# cyclops_r2b.net
KiCad netlist of a schematic drawn in EAGLE
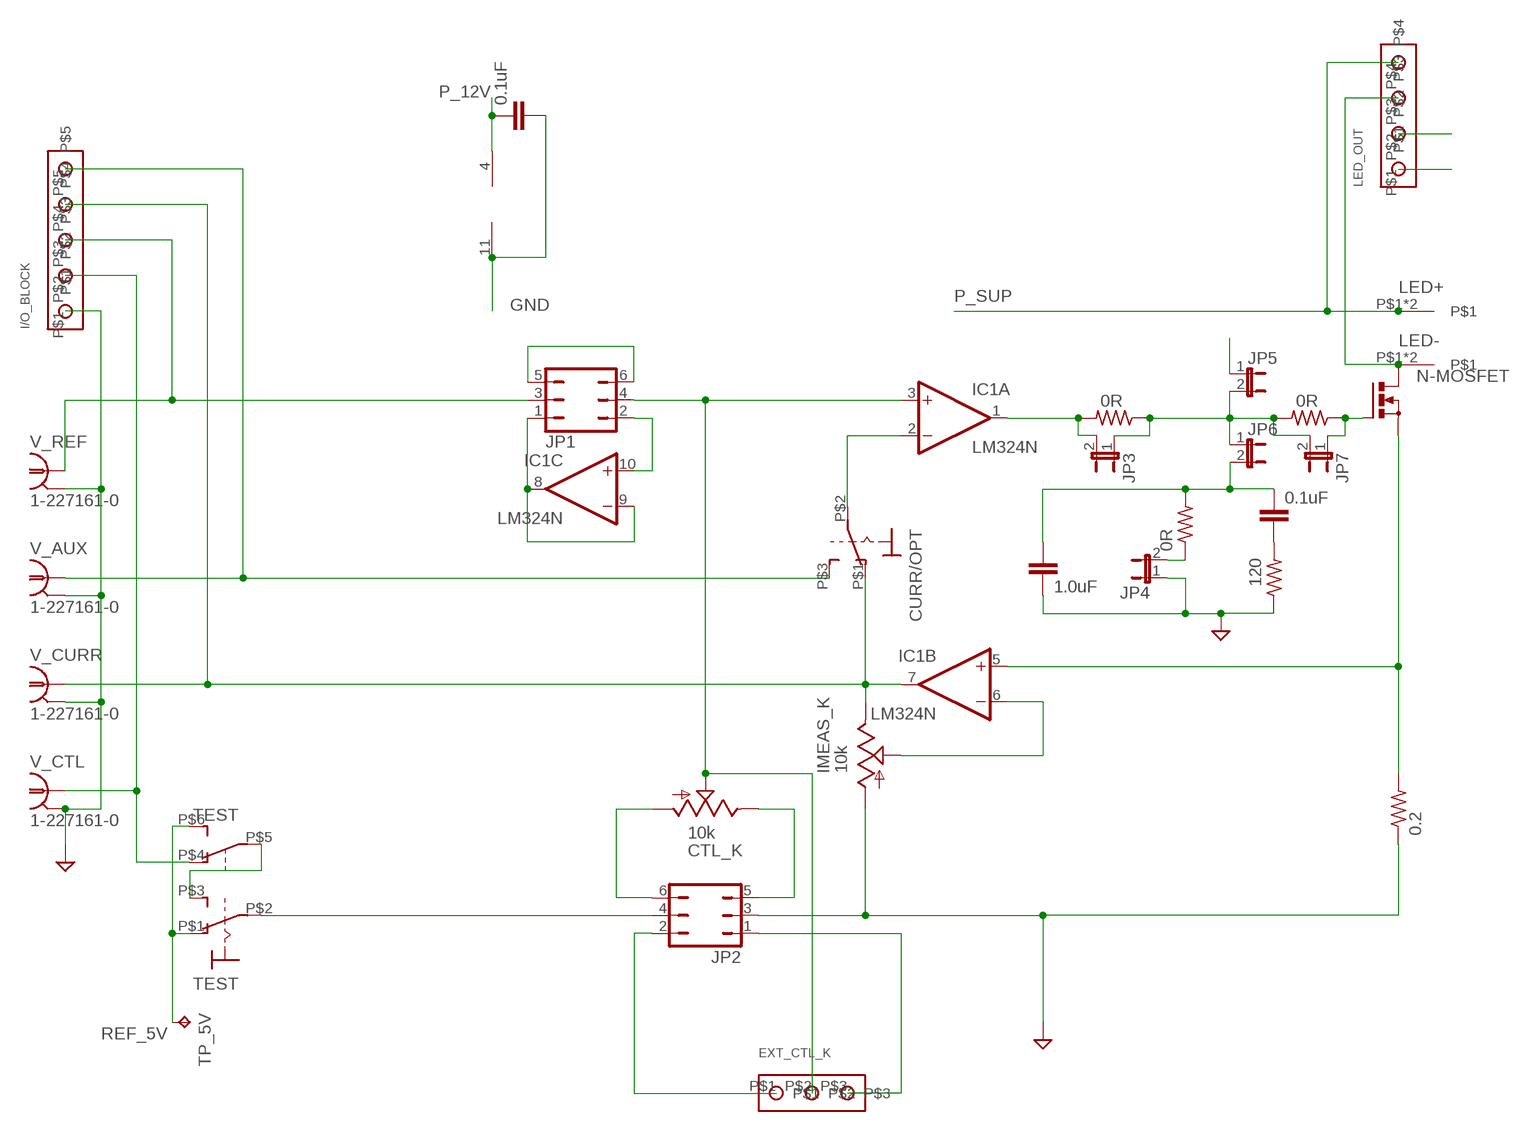
[diagram p0: schematic, sheet 1]
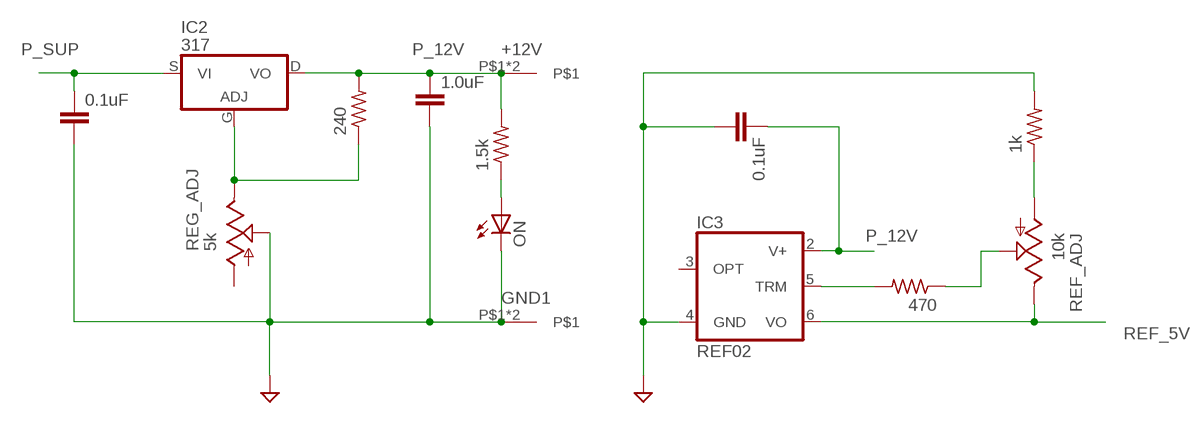
[diagram p1: schematic, sheet 2]
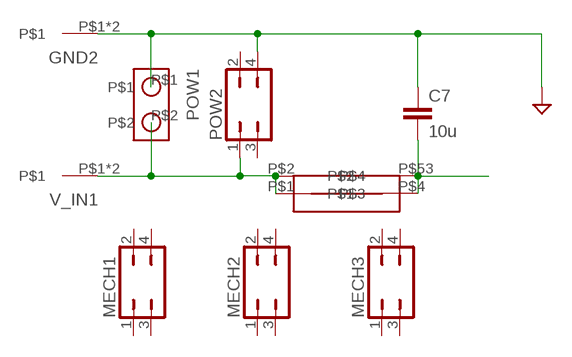
[diagram p2: schematic, sheet 3]

(export (version "E")
  (design (tool "Eeschema 10.0.6"))
  (components
    (comp (ref "+12V")
      (value "BANANA_TO_BOARD")
      (footprint "eagle-import:BANANA_TO_BOARD")
      (libsource (lib "eagle-import") (part "BANANA_TO_BOARD"))
    )
    (comp (ref "C4")
      (value "0.1uF")
      (footprint "eagle-import:C050-024X044")
      (libsource (lib "eagle-import") (part "C-EU050-024X044"))
    )
    (comp (ref "C5")
      (value "1.0uF")
      (footprint "eagle-import:C025-024X044")
      (libsource (lib "eagle-import") (part "C-EU025-024X044"))
    )
    (comp (ref "C6")
      (value "0.1uF")
      (footprint "eagle-import:C050-024X044")
      (libsource (lib "eagle-import") (part "C-EU050-024X044"))
    )
    (comp (ref "GND1")
      (value "BANANA_TO_BOARD")
      (footprint "eagle-import:BANANA_TO_BOARD")
      (libsource (lib "eagle-import") (part "BANANA_TO_BOARD"))
    )
    (comp (ref "IC2")
      (value "317")
      (footprint "eagle-import:TO220BH")
      (libsource (lib "eagle-import") (part "317"))
    )
    (comp (ref "IC3")
      (value "REF02")
      (footprint "eagle-import:DIL08-OVAL")
      (libsource (lib "eagle-import") (part "REF02DIL08-LONG"))
    )
    (comp (ref "ON")
      (value "LED3MM")
      (footprint "eagle-import:LED3MM")
      (libsource (lib "eagle-import") (part "LED3MM"))
    )
    (comp (ref "R5")
      (value "240")
      (footprint "eagle-import:0207_7")
      (libsource (lib "eagle-import") (part "R-US_0207/7"))
    )
    (comp (ref "R6")
      (value "1.5k")
      (footprint "eagle-import:0207_7")
      (libsource (lib "eagle-import") (part "R-US_0207/7"))
    )
    (comp (ref "R7")
      (value "470")
      (footprint "eagle-import:0207_7")
      (libsource (lib "eagle-import") (part "R-US_0207/7"))
    )
    (comp (ref "R8")
      (value "1k")
      (footprint "eagle-import:0207_7")
      (libsource (lib "eagle-import") (part "R-US_0207/7"))
    )
    (comp (ref "REF_ADJ")
      (value "10k")
      (footprint "eagle-import:RJ6S")
      (libsource (lib "eagle-import") (part "TRIM_US-RJ6S"))
    )
    (comp (ref "REG_ADJ")
      (value "5k")
      (footprint "eagle-import:RJ6S")
      (libsource (lib "eagle-import") (part "TRIM_US-RJ6S"))
    )
    (comp (ref "C7")
      (value "10u")
      (footprint "eagle-import:C025-024X044")
      (libsource (lib "eagle-import") (part "C-EU025-024X044"))
    )
    (comp (ref "GND2")
      (value "BANANA_TO_BOARD")
      (footprint "eagle-import:BANANA_TO_BOARD")
      (libsource (lib "eagle-import") (part "BANANA_TO_BOARD"))
    )
    (comp (ref "MECH1")
      (value "JP2Q")
      (footprint "eagle-import:JP2Q")
      (libsource (lib "eagle-import") (part "JP2Q"))
    )
    (comp (ref "MECH2")
      (value "JP2Q")
      (footprint "eagle-import:JP2Q")
      (libsource (lib "eagle-import") (part "JP2Q"))
    )
    (comp (ref "MECH3")
      (value "JP2Q")
      (footprint "eagle-import:JP2Q")
      (libsource (lib "eagle-import") (part "JP2Q"))
    )
    (comp (ref "POW1")
      (value "SCREW2")
      (footprint "eagle-import:SCREW2")
      (libsource (lib "eagle-import") (part "SCREW2"))
    )
    (comp (ref "POW2")
      (value "JP2Q")
      (footprint "eagle-import:JP2Q")
      (libsource (lib "eagle-import") (part "JP2Q"))
    )
    (comp (ref "U$1")
      (value "FUSE >2A")
      (footprint "eagle-import:NXT-FUSE")
      (libsource (lib "eagle-import") (part "NXT-FUSE"))
    )
    (comp (ref "V_IN1")
      (value "BANANA_TO_BOARD")
      (footprint "eagle-import:BANANA_TO_BOARD")
      (libsource (lib "eagle-import") (part "BANANA_TO_BOARD"))
    )
    (comp (ref "C1")
      (value "0.1uF")
      (footprint "eagle-import:C050-024X044")
      (libsource (lib "eagle-import") (part "C-EU050-024X044"))
    )
    (comp (ref "C2")
      (value "1.0uF")
      (footprint "eagle-import:C025-024X044")
      (libsource (lib "eagle-import") (part "C-EU025-024X044"))
    )
    (comp (ref "C3")
      (value "0.1uF")
      (footprint "eagle-import:C050-024X044")
      (libsource (lib "eagle-import") (part "C-EU050-024X044"))
    )
    (comp (ref "CTL_K")
      (value "10k")
      (footprint "eagle-import:RJ6S")
      (libsource (lib "eagle-import") (part "TRIM_US-RJ6S"))
    )
    (comp (ref "CURR/OPT")
      (value "SPST_SWITCH")
      (footprint "eagle-import:A_TOGGLE_SPST")
      (libsource (lib "eagle-import") (part "SPST_SWITCH"))
    )
    (comp (ref "EXT_CTL_K")
      (value "SCREW3")
      (footprint "eagle-import:SCREW3")
      (libsource (lib "eagle-import") (part "SCREW3"))
    )
    (comp (ref "I/O_BLOCK")
      (value "SCREW5")
      (footprint "eagle-import:SCREW5")
      (libsource (lib "eagle-import") (part "SCREW5"))
    )
    (comp (ref "IC1")
      (value "LM324N")
      (footprint "eagle-import:DIL14")
      (libsource (lib "eagle-import") (part "LM324N"))
    )
    (comp (ref "IMEAS_K")
      (value "10k")
      (footprint "eagle-import:RJ6S")
      (libsource (lib "eagle-import") (part "TRIM_US-RJ6S"))
    )
    (comp (ref "JP1")
      (value "JP3Q")
      (footprint "eagle-import:JP3Q")
      (libsource (lib "eagle-import") (part "JP3Q"))
    )
    (comp (ref "JP2")
      (value "JP3Q")
      (footprint "eagle-import:JP3Q")
      (libsource (lib "eagle-import") (part "JP3Q"))
    )
    (comp (ref "JP3")
      (value "JP1E")
      (footprint "eagle-import:JP1")
      (libsource (lib "eagle-import") (part "JP1E"))
    )
    (comp (ref "JP4")
      (value "JP1E")
      (footprint "eagle-import:JP1")
      (libsource (lib "eagle-import") (part "JP1E"))
    )
    (comp (ref "JP5")
      (value "JP1E")
      (footprint "eagle-import:JP1")
      (libsource (lib "eagle-import") (part "JP1E"))
    )
    (comp (ref "JP6")
      (value "JP1E")
      (footprint "eagle-import:JP1")
      (libsource (lib "eagle-import") (part "JP1E"))
    )
    (comp (ref "JP7")
      (value "JP1E")
      (footprint "eagle-import:JP1")
      (libsource (lib "eagle-import") (part "JP1E"))
    )
    (comp (ref "LED+")
      (value "BANANA_TO_BOARD")
      (footprint "eagle-import:BANANA_TO_BOARD")
      (libsource (lib "eagle-import") (part "BANANA_TO_BOARD"))
    )
    (comp (ref "LED-")
      (value "BANANA_TO_BOARD")
      (footprint "eagle-import:BANANA_TO_BOARD")
      (libsource (lib "eagle-import") (part "BANANA_TO_BOARD"))
    )
    (comp (ref "LED_OUT")
      (value "SCREW4")
      (footprint "eagle-import:SCREW4")
      (libsource (lib "eagle-import") (part "SCREW4"))
    )
    (comp (ref "N-MOSFET")
      (value "PMOSFET_NTO220BH")
      (footprint "eagle-import:TO220BH")
      (libsource (lib "eagle-import") (part "PMOSFET_NTO220BH"))
    )
    (comp (ref "R1")
      (value "0R")
      (footprint "eagle-import:0207_7")
      (libsource (lib "eagle-import") (part "R-US_0207/7"))
    )
    (comp (ref "R2")
      (value "0R")
      (footprint "eagle-import:0207_7")
      (libsource (lib "eagle-import") (part "R-US_0207/7"))
    )
    (comp (ref "R3")
      (value "120")
      (footprint "eagle-import:0207_7")
      (libsource (lib "eagle-import") (part "R-US_0207/7"))
    )
    (comp (ref "R4")
      (value "0R")
      (footprint "eagle-import:0207_7")
      (libsource (lib "eagle-import") (part "R-US_0207/7"))
    )
    (comp (ref "R_CURR")
      (value "0.2")
      (footprint "eagle-import:IMEAS_R")
      (libsource (lib "eagle-import") (part "R-US_"))
    )
    (comp (ref "TEST")
      (value "SP3T_SWITCH")
      (footprint "eagle-import:320-938")
      (libsource (lib "eagle-import") (part "SP3T_SWITCH"))
    )
    (comp (ref "TP_5V")
      (value "TPPAD1-13")
      (footprint "eagle-import:P1-13")
      (libsource (lib "eagle-import") (part "TPPAD1-13"))
    )
    (comp (ref "V_AUX")
      (value "1-227161-0")
      (footprint "eagle-import:AMP_227161")
      (libsource (lib "eagle-import") (part "?2271611--0"))
    )
    (comp (ref "V_CTL")
      (value "1-227161-0")
      (footprint "eagle-import:AMP_227161")
      (libsource (lib "eagle-import") (part "?2271611--0"))
    )
    (comp (ref "V_CURR")
      (value "1-227161-0")
      (footprint "eagle-import:AMP_227161")
      (libsource (lib "eagle-import") (part "?2271611--0"))
    )
    (comp (ref "V_REF")
      (value "1-227161-0")
      (footprint "eagle-import:AMP_227161")
      (libsource (lib "eagle-import") (part "?2271611--0"))
    )
  )
  (nets
    (net (code "1") (name "GND") (class "Default")
      (node (ref "C1") (pin "2") (pinfunction "2_2") (pintype "passive"))
      (node (ref "C2") (pin "2") (pinfunction "2_2") (pintype "passive"))
      (node (ref "C4") (pin "2") (pinfunction "2_2") (pintype "passive"))
      (node (ref "C5") (pin "2") (pinfunction "2_2") (pintype "passive"))
      (node (ref "C6") (pin "2") (pinfunction "2_2") (pintype "passive"))
      (node (ref "C7") (pin "1") (pinfunction "1_1") (pintype "passive"))
      (node (ref "GND1") (pin "P$1") (pinfunction "P$1_P$1") (pintype "bidirectional"))
      (node (ref "GND1") (pin "P$2") (pinfunction "P$1_P$2") (pintype "bidirectional"))
      (node (ref "GND2") (pin "P$1") (pinfunction "P$1_P$1") (pintype "bidirectional"))
      (node (ref "GND2") (pin "P$2") (pinfunction "P$1_P$2") (pintype "bidirectional"))
      (node (ref "I/O_BLOCK") (pin "P$1") (pinfunction "P$1_P$1") (pintype "bidirectional"))
      (node (ref "IC1") (pin "11") (pinfunction "V-_11") (pintype "power_in"))
      (node (ref "IC3") (pin "4") (pinfunction "GND_4") (pintype "power_in"))
      (node (ref "IMEAS_K") (pin "A") (pinfunction "A_A") (pintype "passive"))
      (node (ref "JP2") (pin "3") (pinfunction "3_3") (pintype "passive"))
      (node (ref "JP4") (pin "1") (pinfunction "1_1") (pintype "passive"))
      (node (ref "LED_OUT") (pin "P$1") (pinfunction "P$1_P$1") (pintype "bidirectional"))
      (node (ref "ON") (pin "K") (pinfunction "C_K") (pintype "passive"))
      (node (ref "POW1") (pin "P$1") (pinfunction "P$1_P$1") (pintype "bidirectional"))
      (node (ref "POW2") (pin "4") (pinfunction "4_4") (pintype "passive"))
      (node (ref "R3") (pin "1") (pinfunction "1_1") (pintype "passive"))
      (node (ref "R8") (pin "2") (pinfunction "2_2") (pintype "passive"))
      (node (ref "REG_ADJ") (pin "S") (pinfunction "S_S") (pintype "passive"))
      (node (ref "R_CURR") (pin "1") (pinfunction "1_1") (pintype "passive"))
      (node (ref "V_AUX") (pin "2") (pinfunction "GND_2") (pintype "power_in"))
      (node (ref "V_CTL") (pin "2") (pinfunction "GND_2") (pintype "power_in"))
      (node (ref "V_CURR") (pin "2") (pinfunction "GND_2") (pintype "power_in"))
      (node (ref "V_REF") (pin "2") (pinfunction "GND_2") (pintype "power_in"))
    )
    (net (code "2") (name "Net-(C2-Pad1)") (class "Default")
      (node (ref "C2") (pin "1") (pinfunction "1_1") (pintype "passive"))
      (node (ref "C3") (pin "1") (pinfunction "1_1") (pintype "passive"))
      (node (ref "JP6") (pin "2") (pinfunction "2_2") (pintype "passive"))
      (node (ref "R2") (pin "2") (pinfunction "2_2") (pintype "passive"))
    )
    (net (code "3") (name "Net-(C3-Pad2)") (class "Default")
      (node (ref "C3") (pin "2") (pinfunction "2_2") (pintype "passive"))
      (node (ref "R3") (pin "2") (pinfunction "2_2") (pintype "passive"))
    )
    (net (code "4") (name "Net-(CTL_K-PadA)") (class "Default")
      (node (ref "CTL_K") (pin "A") (pinfunction "A_A") (pintype "passive"))
      (node (ref "JP2") (pin "6") (pinfunction "6_6") (pintype "passive"))
    )
    (net (code "5") (name "Net-(CTL_K-PadE)") (class "Default")
      (node (ref "CTL_K") (pin "E") (pinfunction "E_E") (pintype "passive"))
      (node (ref "JP2") (pin "5") (pinfunction "5_5") (pintype "passive"))
    )
    (net (code "6") (name "Net-(CURR/OPT-O)") (class "Default")
      (node (ref "CURR/OPT") (pin "P$1") (pinfunction "O_P$1") (pintype "passive"))
      (node (ref "I/O_BLOCK") (pin "P$4") (pinfunction "P$4_P$4") (pintype "bidirectional"))
      (node (ref "IC1") (pin "7") (pinfunction "OUT_7") (pintype "output"))
      (node (ref "IMEAS_K") (pin "E") (pinfunction "E_E") (pintype "passive"))
      (node (ref "V_CURR") (pin "1") (pinfunction "1_1") (pintype "passive"))
    )
    (net (code "7") (name "Net-(CURR/OPT-P)") (class "Default")
      (node (ref "CURR/OPT") (pin "P$2") (pinfunction "P_P$2") (pintype "passive"))
      (node (ref "IC1") (pin "2") (pinfunction "-IN_2") (pintype "input"))
    )
    (net (code "8") (name "Net-(CURR/OPT-S)") (class "Default")
      (node (ref "CURR/OPT") (pin "P$3") (pinfunction "S_P$3") (pintype "passive"))
      (node (ref "I/O_BLOCK") (pin "P$5") (pinfunction "P$5_P$5") (pintype "bidirectional"))
      (node (ref "V_AUX") (pin "1") (pinfunction "1_1") (pintype "passive"))
    )
    (net (code "9") (name "Net-(EXT_CTL_K-PadP$1)") (class "Default")
      (node (ref "EXT_CTL_K") (pin "P$1") (pinfunction "P$1_P$1") (pintype "bidirectional"))
      (node (ref "JP2") (pin "2") (pinfunction "2_2") (pintype "passive"))
    )
    (net (code "10") (name "Net-(EXT_CTL_K-PadP$3)") (class "Default")
      (node (ref "EXT_CTL_K") (pin "P$3") (pinfunction "P$3_P$3") (pintype "bidirectional"))
      (node (ref "JP2") (pin "1") (pinfunction "1_1") (pintype "passive"))
    )
    (net (code "11") (name "Net-(I/O_BLOCK-PadP$3)") (class "Default")
      (node (ref "I/O_BLOCK") (pin "P$3") (pinfunction "P$3_P$3") (pintype "bidirectional"))
      (node (ref "JP1") (pin "3") (pinfunction "3_3") (pintype "passive"))
      (node (ref "V_REF") (pin "1") (pinfunction "1_1") (pintype "passive"))
    )
    (net (code "12") (name "Net-(IC1A-+IN)") (class "Default")
      (node (ref "CTL_K") (pin "S") (pinfunction "S_S") (pintype "passive"))
      (node (ref "EXT_CTL_K") (pin "P$2") (pinfunction "P$2_P$2") (pintype "bidirectional"))
      (node (ref "IC1") (pin "3") (pinfunction "+IN_3") (pintype "input"))
      (node (ref "JP1") (pin "4") (pinfunction "4_4") (pintype "passive"))
    )
    (net (code "13") (name "Net-(IC1A-OUT)") (class "Default")
      (node (ref "IC1") (pin "1") (pinfunction "OUT_1") (pintype "output"))
      (node (ref "JP3") (pin "2") (pinfunction "2_2") (pintype "passive"))
      (node (ref "R1") (pin "2") (pinfunction "2_2") (pintype "passive"))
    )
    (net (code "14") (name "Net-(IC1B-+IN)") (class "Default")
      (node (ref "IC1") (pin "5") (pinfunction "+IN_5") (pintype "input"))
      (node (ref "N-MOSFET") (pin "S") (pinfunction "S_S") (pintype "passive"))
      (node (ref "R_CURR") (pin "2") (pinfunction "2_2") (pintype "passive"))
    )
    (net (code "15") (name "Net-(IC1B--IN)") (class "Default")
      (node (ref "IC1") (pin "6") (pinfunction "-IN_6") (pintype "input"))
      (node (ref "IMEAS_K") (pin "S") (pinfunction "S_S") (pintype "passive"))
    )
    (net (code "16") (name "Net-(IC1C-+IN)") (class "Default")
      (node (ref "IC1") (pin "10") (pinfunction "+IN_10") (pintype "input"))
      (node (ref "JP1") (pin "2") (pinfunction "2_2") (pintype "passive"))
    )
    (net (code "17") (name "Net-(IC1C--IN)") (class "Default")
      (node (ref "IC1") (pin "8") (pinfunction "OUT_8") (pintype "output"))
      (node (ref "IC1") (pin "9") (pinfunction "-IN_9") (pintype "input"))
      (node (ref "JP1") (pin "1") (pinfunction "1_1") (pintype "passive"))
    )
    (net (code "18") (name "Net-(IC2-ADJ)") (class "Default")
      (node (ref "IC2") (pin "G") (pinfunction "ADJ_G") (pintype "input"))
      (node (ref "R5") (pin "1") (pinfunction "1_1") (pintype "passive"))
      (node (ref "REG_ADJ") (pin "E") (pinfunction "E_E") (pintype "passive"))
    )
    (net (code "19") (name "Net-(IC3-TRM)") (class "Default")
      (node (ref "IC3") (pin "5") (pinfunction "TRM_5") (pintype "input"))
      (node (ref "R7") (pin "2") (pinfunction "2_2") (pintype "passive"))
    )
    (net (code "20") (name "Net-(JP1-Pad5)") (class "Default")
      (node (ref "JP1") (pin "5") (pinfunction "5_5") (pintype "passive"))
      (node (ref "JP1") (pin "6") (pinfunction "6_6") (pintype "passive"))
    )
    (net (code "21") (name "Net-(JP3-Pad1)") (class "Default")
      (node (ref "JP3") (pin "1") (pinfunction "1_1") (pintype "passive"))
      (node (ref "JP5") (pin "2") (pinfunction "2_2") (pintype "passive"))
      (node (ref "JP6") (pin "1") (pinfunction "1_1") (pintype "passive"))
      (node (ref "JP7") (pin "2") (pinfunction "2_2") (pintype "passive"))
      (node (ref "R1") (pin "1") (pinfunction "1_1") (pintype "passive"))
      (node (ref "R4") (pin "2") (pinfunction "2_2") (pintype "passive"))
    )
    (net (code "22") (name "Net-(JP4-Pad2)") (class "Default")
      (node (ref "JP4") (pin "2") (pinfunction "2_2") (pintype "passive"))
      (node (ref "R2") (pin "1") (pinfunction "1_1") (pintype "passive"))
    )
    (net (code "23") (name "Net-(JP7-Pad1)") (class "Default")
      (node (ref "JP7") (pin "1") (pinfunction "1_1") (pintype "passive"))
      (node (ref "N-MOSFET") (pin "G") (pinfunction "G_G") (pintype "passive"))
      (node (ref "R4") (pin "1") (pinfunction "1_1") (pintype "passive"))
    )
    (net (code "24") (name "Net-(LED--P$1-PadP$2)") (class "Default")
      (node (ref "LED-") (pin "P$1") (pinfunction "P$1_P$1") (pintype "bidirectional"))
      (node (ref "LED-") (pin "P$2") (pinfunction "P$1_P$2") (pintype "bidirectional"))
      (node (ref "LED_OUT") (pin "P$3") (pinfunction "P$3_P$3") (pintype "bidirectional"))
      (node (ref "N-MOSFET") (pin "D") (pinfunction "D_D") (pintype "passive"))
    )
    (net (code "25") (name "Net-(ON-PadA)") (class "Default")
      (node (ref "ON") (pin "A") (pinfunction "A_A") (pintype "passive"))
      (node (ref "R6") (pin "1") (pinfunction "1_1") (pintype "passive"))
    )
    (net (code "26") (name "Net-(POW1-PadP$2)") (class "Default")
      (node (ref "POW1") (pin "P$2") (pinfunction "P$2_P$2") (pintype "bidirectional"))
      (node (ref "POW2") (pin "1") (pinfunction "1_1") (pintype "passive"))
      (node (ref "U$1") (pin "P$1") (pinfunction "P$1_P$1") (pintype "bidirectional"))
      (node (ref "U$1") (pin "P$2") (pinfunction "P$2_P$2") (pintype "bidirectional"))
      (node (ref "V_IN1") (pin "P$1") (pinfunction "P$1_P$1") (pintype "bidirectional"))
      (node (ref "V_IN1") (pin "P$2") (pinfunction "P$1_P$2") (pintype "bidirectional"))
    )
    (net (code "27") (name "Net-(R7-Pad1)") (class "Default")
      (node (ref "R7") (pin "1") (pinfunction "1_1") (pintype "passive"))
      (node (ref "REF_ADJ") (pin "S") (pinfunction "S_S") (pintype "passive"))
    )
    (net (code "28") (name "Net-(R8-Pad1)") (class "Default")
      (node (ref "R8") (pin "1") (pinfunction "1_1") (pintype "passive"))
      (node (ref "REF_ADJ") (pin "A") (pinfunction "A_A") (pintype "passive"))
    )
    (net (code "29") (name "Net-(TESTA-P)") (class "Default")
      (node (ref "JP2") (pin "4") (pinfunction "4_4") (pintype "passive"))
      (node (ref "TEST") (pin "P$2") (pinfunction "P_P$2") (pintype "passive"))
    )
    (net (code "30") (name "Net-(TESTA-S)") (class "Default")
      (node (ref "TEST") (pin "P$3") (pinfunction "S_P$3") (pintype "passive"))
      (node (ref "TEST") (pin "P$5") (pinfunction "P_P$5") (pintype "passive"))
    )
    (net (code "31") (name "Net-(TESTB-O)") (class "Default")
      (node (ref "I/O_BLOCK") (pin "P$2") (pinfunction "P$2_P$2") (pintype "bidirectional"))
      (node (ref "TEST") (pin "P$4") (pinfunction "O_P$4") (pintype "passive"))
      (node (ref "V_CTL") (pin "1") (pinfunction "1_1") (pintype "passive"))
    )
    (net (code "32") (name "P_12V") (class "Default")
      (node (ref "+12V") (pin "P$1") (pinfunction "P$1_P$1") (pintype "bidirectional"))
      (node (ref "+12V") (pin "P$2") (pinfunction "P$1_P$2") (pintype "bidirectional"))
      (node (ref "C1") (pin "1") (pinfunction "1_1") (pintype "passive"))
      (node (ref "C5") (pin "1") (pinfunction "1_1") (pintype "passive"))
      (node (ref "C6") (pin "1") (pinfunction "1_1") (pintype "passive"))
      (node (ref "IC1") (pin "4") (pinfunction "V+_4") (pintype "power_in"))
      (node (ref "IC2") (pin "D") (pinfunction "VO_D") (pintype "passive"))
      (node (ref "IC3") (pin "2") (pinfunction "V+_2") (pintype "power_in"))
      (node (ref "LED_OUT") (pin "P$2") (pinfunction "P$2_P$2") (pintype "bidirectional"))
      (node (ref "R5") (pin "2") (pinfunction "2_2") (pintype "passive"))
      (node (ref "R6") (pin "2") (pinfunction "2_2") (pintype "passive"))
    )
    (net (code "33") (name "P_SUP") (class "Default")
      (node (ref "C4") (pin "1") (pinfunction "1_1") (pintype "passive"))
      (node (ref "C7") (pin "2") (pinfunction "2_2") (pintype "passive"))
      (node (ref "IC2") (pin "S") (pinfunction "VI_S") (pintype "input"))
      (node (ref "LED+") (pin "P$1") (pinfunction "P$1_P$1") (pintype "bidirectional"))
      (node (ref "LED+") (pin "P$2") (pinfunction "P$1_P$2") (pintype "bidirectional"))
      (node (ref "LED_OUT") (pin "P$4") (pinfunction "P$4_P$4") (pintype "bidirectional"))
      (node (ref "U$1") (pin "P$4") (pinfunction "P$3_P$4") (pintype "bidirectional"))
      (node (ref "U$1") (pin "P$53") (pinfunction "P$4_P$53") (pintype "bidirectional"))
    )
    (net (code "34") (name "REF_5V") (class "Default")
      (node (ref "IC3") (pin "6") (pinfunction "VO_6") (pintype "output"))
      (node (ref "REF_ADJ") (pin "E") (pinfunction "E_E") (pintype "passive"))
      (node (ref "TEST") (pin "P$1") (pinfunction "O_P$1") (pintype "passive"))
      (node (ref "TEST") (pin "P$6") (pinfunction "S_P$6") (pintype "passive"))
      (node (ref "TP_5V") (pin "TP") (pinfunction "TP_TP") (pintype "input"))
    )
    (net (code "35") (name "unconnected-(IC3-OPT-Pad3)") (class "Default")
      (node (ref "IC3") (pin "3") (pinfunction "OPT_3") (pintype "output"))
    )
    (net (code "36") (name "unconnected-(JP5-Pad1)") (class "Default")
      (node (ref "JP5") (pin "1") (pinfunction "1_1") (pintype "passive"))
    )
    (net (code "37") (name "unconnected-(MECH1-Pad1)") (class "Default")
      (node (ref "MECH1") (pin "1") (pinfunction "1_1") (pintype "passive"))
    )
    (net (code "38") (name "unconnected-(MECH1-Pad2)") (class "Default")
      (node (ref "MECH1") (pin "2") (pinfunction "2_2") (pintype "passive"))
    )
    (net (code "39") (name "unconnected-(MECH1-Pad3)") (class "Default")
      (node (ref "MECH1") (pin "3") (pinfunction "3_3") (pintype "passive"))
    )
    (net (code "40") (name "unconnected-(MECH1-Pad4)") (class "Default")
      (node (ref "MECH1") (pin "4") (pinfunction "4_4") (pintype "passive"))
    )
    (net (code "41") (name "unconnected-(MECH2-Pad1)") (class "Default")
      (node (ref "MECH2") (pin "1") (pinfunction "1_1") (pintype "passive"))
    )
    (net (code "42") (name "unconnected-(MECH2-Pad2)") (class "Default")
      (node (ref "MECH2") (pin "2") (pinfunction "2_2") (pintype "passive"))
    )
    (net (code "43") (name "unconnected-(MECH2-Pad3)") (class "Default")
      (node (ref "MECH2") (pin "3") (pinfunction "3_3") (pintype "passive"))
    )
    (net (code "44") (name "unconnected-(MECH2-Pad4)") (class "Default")
      (node (ref "MECH2") (pin "4") (pinfunction "4_4") (pintype "passive"))
    )
    (net (code "45") (name "unconnected-(MECH3-Pad1)") (class "Default")
      (node (ref "MECH3") (pin "1") (pinfunction "1_1") (pintype "passive"))
    )
    (net (code "46") (name "unconnected-(MECH3-Pad2)") (class "Default")
      (node (ref "MECH3") (pin "2") (pinfunction "2_2") (pintype "passive"))
    )
    (net (code "47") (name "unconnected-(MECH3-Pad3)") (class "Default")
      (node (ref "MECH3") (pin "3") (pinfunction "3_3") (pintype "passive"))
    )
    (net (code "48") (name "unconnected-(MECH3-Pad4)") (class "Default")
      (node (ref "MECH3") (pin "4") (pinfunction "4_4") (pintype "passive"))
    )
    (net (code "49") (name "unconnected-(POW2-Pad2)") (class "Default")
      (node (ref "POW2") (pin "2") (pinfunction "2_2") (pintype "passive"))
    )
    (net (code "50") (name "unconnected-(POW2-Pad3)") (class "Default")
      (node (ref "POW2") (pin "3") (pinfunction "3_3") (pintype "passive"))
    )
    (net (code "51") (name "unconnected-(REG_ADJ-PadA)") (class "Default")
      (node (ref "REG_ADJ") (pin "A") (pinfunction "A_A") (pintype "passive"))
    )
  )
)
